# Speed.net
KiCad netlist of a schematic drawn in Altium Designer
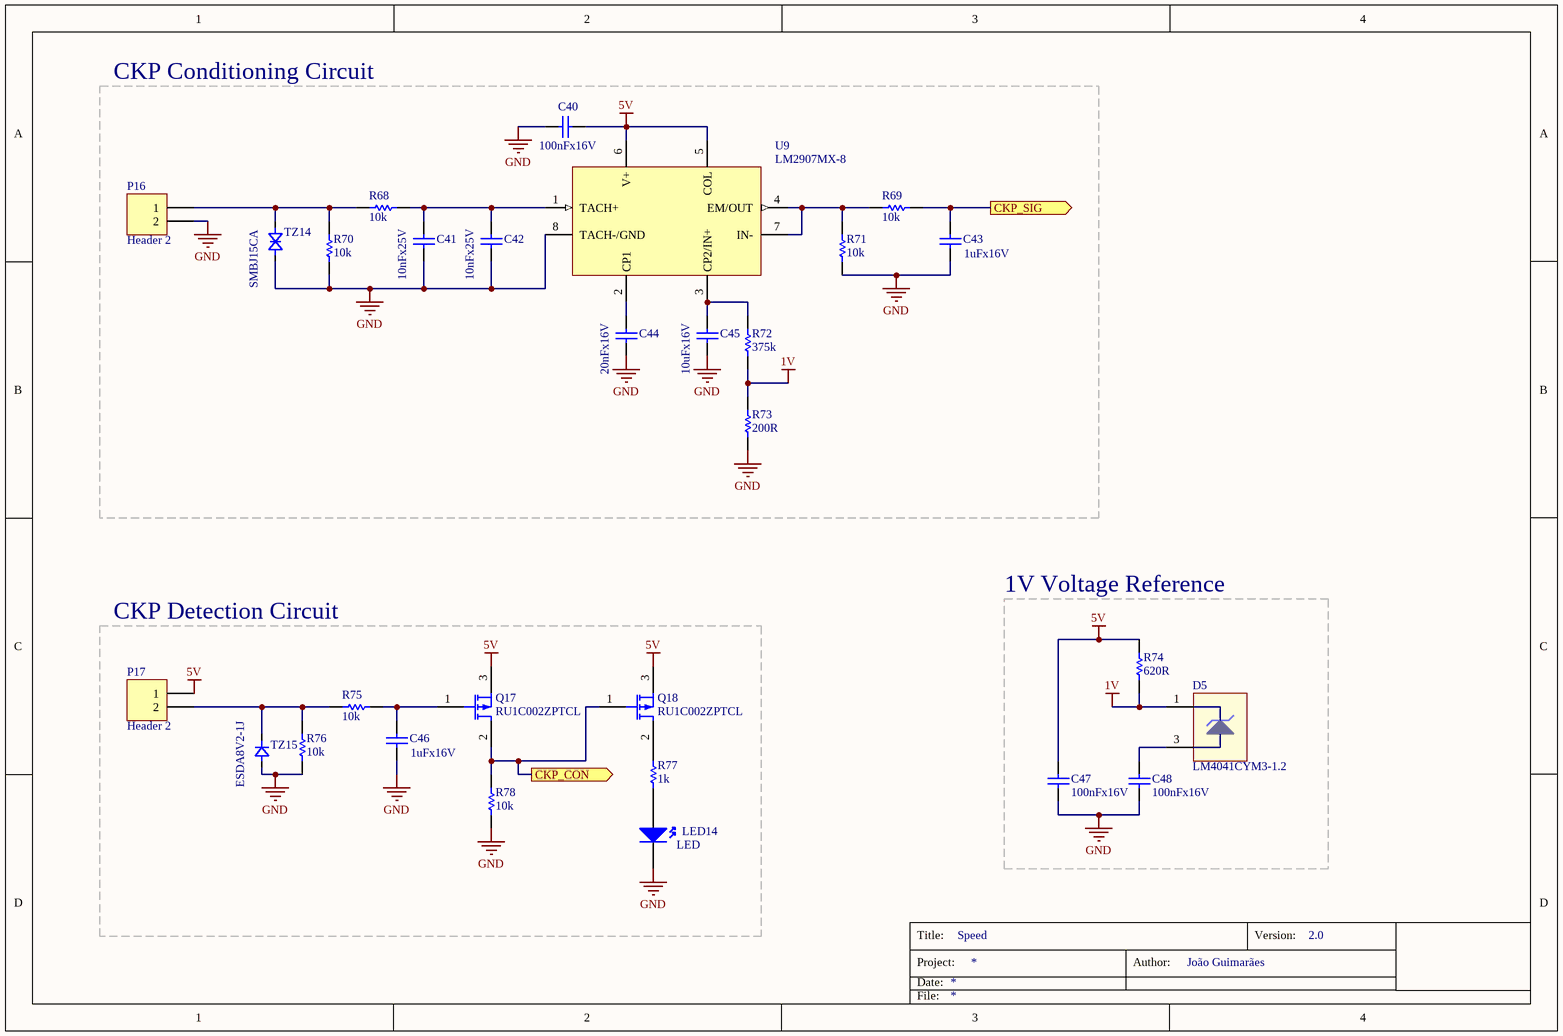
[diagram p0: Speed.SchDoc]

(export (version "E")
  (design (tool "Eeschema 10.0.6"))
  (components
    (comp (ref "C40")
      (value "100nFx16V")
      (footprint "DISC-0805")
      (description "Capacitor")
      (libsource (lib "IntLib") (part "Cap"))
    )
    (comp (ref "C41")
      (value "10nFx25V")
      (footprint "DISC-0805")
      (description "Capacitor")
      (libsource (lib "IntLib") (part "Cap"))
    )
    (comp (ref "C42")
      (value "10nFx25V")
      (footprint "DISC-0805")
      (description "Capacitor")
      (libsource (lib "IntLib") (part "Cap"))
    )
    (comp (ref "C43")
      (value "1uFx16V")
      (footprint "DISC-0805")
      (description "Capacitor")
      (libsource (lib "IntLib") (part "Cap"))
    )
    (comp (ref "C44")
      (value "20nFx16V")
      (footprint "DISC-0805")
      (description "Capacitor")
      (libsource (lib "IntLib") (part "Cap"))
    )
    (comp (ref "C45")
      (value "10uFx16V")
      (footprint "DISC-0805")
      (description "Capacitor")
      (libsource (lib "IntLib") (part "Cap"))
    )
    (comp (ref "C46")
      (value "1uFx16V")
      (footprint "DISC-0805")
      (description "Capacitor")
      (libsource (lib "IntLib") (part "Cap"))
    )
    (comp (ref "C47")
      (value "100nFx16V")
      (footprint "DISC-0805")
      (description "Capacitor")
      (libsource (lib "IntLib") (part "Cap"))
    )
    (comp (ref "C48")
      (value "100nFx16V")
      (footprint "DISC-0805")
      (description "Capacitor")
      (libsource (lib "IntLib") (part "Cap"))
    )
    (comp (ref "D5")
      (value "LM4041CYM3-1.2")
      (footprint "DISC-SOT-23")
      (description "Shunt Voltage References")
      (libsource (lib "IntLib") (part "LM4040"))
    )
    (comp (ref "LED14") (value "LED") (footprint "DISC-LED-0.1-PTH") (libsource (lib "IntLib") (part "LED")))
    (comp (ref "P16")
      (value "Header 2")
      (footprint "CON-FLEXWIRE-0.5MM2-1X2")
      (description "Header, 2-Pin")
      (fields (field (name "PUBLISHER") "Altium Limited"))
      (libsource (lib "IntLib") (part "Header 2"))
    )
    (comp (ref "P17")
      (value "Header 2")
      (footprint "CON-FLEXWIRE-0.5MM2-1X2")
      (description "Header, 2-Pin")
      (fields (field (name "PUBLISHER") "Altium Limited"))
      (libsource (lib "IntLib") (part "Header 2"))
    )
    (comp (ref "Q17")
      (value "RU1C002ZPTCL")
      (footprint "DISC-SOT-23")
      (description "P-Channel MOSFET")
      (libsource (lib "IntLib") (part "Transistor-PMOS"))
    )
    (comp (ref "Q18")
      (value "RU1C002ZPTCL")
      (footprint "DISC-SOT-23")
      (description "P-Channel MOSFET")
      (libsource (lib "IntLib") (part "Transistor-PMOS"))
    )
    (comp (ref "R68")
      (value "10k")
      (footprint "DISC-0805")
      (description "Resistor")
      (libsource (lib "IntLib") (part "Res"))
    )
    (comp (ref "R69")
      (value "10k")
      (footprint "DISC-0805")
      (description "Resistor")
      (libsource (lib "IntLib") (part "Res"))
    )
    (comp (ref "R70")
      (value "10k")
      (footprint "DISC-0805")
      (description "Resistor")
      (libsource (lib "IntLib") (part "Res"))
    )
    (comp (ref "R71")
      (value "10k")
      (footprint "DISC-0805")
      (description "Resistor")
      (libsource (lib "IntLib") (part "Res"))
    )
    (comp (ref "R72")
      (value "375k")
      (footprint "DISC-0805")
      (description "Resistor")
      (libsource (lib "IntLib") (part "Res"))
    )
    (comp (ref "R73")
      (value "200R")
      (footprint "DISC-0805")
      (description "Resistor")
      (libsource (lib "IntLib") (part "Res"))
    )
    (comp (ref "R74")
      (value "620R")
      (footprint "DISC-0805")
      (description "Resistor")
      (libsource (lib "IntLib") (part "Res"))
    )
    (comp (ref "R75")
      (value "10k")
      (footprint "DISC-0805")
      (description "Resistor")
      (libsource (lib "IntLib") (part "Res"))
    )
    (comp (ref "R76")
      (value "10k")
      (footprint "DISC-0805")
      (description "Resistor")
      (libsource (lib "IntLib") (part "Res"))
    )
    (comp (ref "R77")
      (value "1k")
      (footprint "DISC-0805")
      (description "Resistor")
      (libsource (lib "IntLib") (part "Res"))
    )
    (comp (ref "R78")
      (value "10k")
      (footprint "DISC-0805")
      (description "Resistor")
      (libsource (lib "IntLib") (part "Res"))
    )
    (comp (ref "TZ14")
      (value "SMBJ15CA")
      (footprint "DISC-DO214-AA")
      (description "TVZ-Bi-Directional")
      (libsource (lib "IntLib") (part "TVZ-Bi-Directional"))
    )
    (comp (ref "TZ15")
      (value "ESDA8V2-1J")
      (footprint "DISC-SOD-323")
      (description "TVZ-Unidirectional")
      (libsource (lib "IntLib") (part "TVZ-Unidirectional"))
    )
    (comp (ref "U9")
      (value "LM2907MX-8")
      (footprint "CI-SOIC-8")
      (description "Voltage to Frequency & Frequency to Voltage Frequency to Voltage Converter")
      (libsource (lib "IntLib") (part "LM2907MX-8"))
    )
  )
  (nets
    (net (code "1") (name "/CKP_CON") (class "Default")
      (node (ref "Q17") (pin "2") (pinfunction "D_2") (pintype "passive"))
      (node (ref "Q18") (pin "1") (pinfunction "G_1") (pintype "passive"))
      (node (ref "R78") (pin "2") (pinfunction "2_2") (pintype "passive"))
    )
    (net (code "2") (name "/CKP_SIG") (class "Default")
      (node (ref "C43") (pin "2") (pinfunction "2_2") (pintype "passive"))
      (node (ref "R69") (pin "2") (pinfunction "2_2") (pintype "passive"))
    )
    (net (code "3") (name "1V") (class "Default")
      (node (ref "D5") (pin "1") (pinfunction "A_1") (pintype "passive"))
      (node (ref "R72") (pin "2") (pinfunction "2_2") (pintype "passive"))
      (node (ref "R73") (pin "1") (pinfunction "1_1") (pintype "passive"))
      (node (ref "R74") (pin "2") (pinfunction "2_2") (pintype "passive"))
    )
    (net (code "4") (name "5V") (class "Default")
      (node (ref "C40") (pin "1") (pinfunction "1_1") (pintype "passive"))
      (node (ref "C47") (pin "1") (pinfunction "1_1") (pintype "passive"))
      (node (ref "P17") (pin "1") (pinfunction "1_1") (pintype "passive"))
      (node (ref "Q17") (pin "3") (pinfunction "S_3") (pintype "passive"))
      (node (ref "Q18") (pin "3") (pinfunction "S_3") (pintype "passive"))
      (node (ref "R74") (pin "1") (pinfunction "1_1") (pintype "passive"))
      (node (ref "U9") (pin "5") (pinfunction "COL_5") (pintype "passive"))
      (node (ref "U9") (pin "6") (pinfunction "V+_6") (pintype "power_in"))
    )
    (net (code "5") (name "GND") (class "Default")
      (node (ref "C40") (pin "2") (pinfunction "2_2") (pintype "passive"))
      (node (ref "C41") (pin "1") (pinfunction "1_1") (pintype "passive"))
      (node (ref "C42") (pin "1") (pinfunction "1_1") (pintype "passive"))
      (node (ref "C43") (pin "1") (pinfunction "1_1") (pintype "passive"))
      (node (ref "C44") (pin "1") (pinfunction "1_1") (pintype "passive"))
      (node (ref "C45") (pin "1") (pinfunction "1_1") (pintype "passive"))
      (node (ref "C46") (pin "1") (pinfunction "1_1") (pintype "passive"))
      (node (ref "C47") (pin "2") (pinfunction "2_2") (pintype "passive"))
      (node (ref "C48") (pin "2") (pinfunction "2_2") (pintype "passive"))
      (node (ref "LED14") (pin "2") (pinfunction "K_2") (pintype "passive"))
      (node (ref "P16") (pin "2") (pinfunction "2_2") (pintype "passive"))
      (node (ref "R70") (pin "2") (pinfunction "2_2") (pintype "passive"))
      (node (ref "R71") (pin "2") (pinfunction "2_2") (pintype "passive"))
      (node (ref "R73") (pin "2") (pinfunction "2_2") (pintype "passive"))
      (node (ref "R76") (pin "2") (pinfunction "2_2") (pintype "passive"))
      (node (ref "R78") (pin "1") (pinfunction "1_1") (pintype "passive"))
      (node (ref "TZ14") (pin "1") (pinfunction "A_1") (pintype "passive"))
      (node (ref "TZ15") (pin "1") (pinfunction "A_1") (pintype "passive"))
      (node (ref "U9") (pin "8") (pinfunction "TACH-/GND_8") (pintype "power_in"))
    )
    (net (code "6") (name "Net-(D5-K)") (class "Default")
      (node (ref "C48") (pin "1") (pinfunction "1_1") (pintype "passive"))
      (node (ref "D5") (pin "3") (pinfunction "K_3") (pintype "passive"))
    )
    (net (code "7") (name "Net-(LED14-A)") (class "Default")
      (node (ref "LED14") (pin "1") (pinfunction "A_1") (pintype "passive"))
      (node (ref "R77") (pin "1") (pinfunction "1_1") (pintype "passive"))
    )
    (net (code "8") (name "Net-(Q17-G)") (class "Default")
      (node (ref "C46") (pin "2") (pinfunction "2_2") (pintype "passive"))
      (node (ref "Q17") (pin "1") (pinfunction "G_1") (pintype "passive"))
      (node (ref "R75") (pin "2") (pinfunction "2_2") (pintype "passive"))
    )
    (net (code "9") (name "Net-(Q18-D)") (class "Default")
      (node (ref "Q18") (pin "2") (pinfunction "D_2") (pintype "passive"))
      (node (ref "R77") (pin "2") (pinfunction "2_2") (pintype "passive"))
    )
    (net (code "10") (name "Net-(TZ14-K)") (class "Default")
      (node (ref "P16") (pin "1") (pinfunction "1_1") (pintype "passive"))
      (node (ref "R68") (pin "2") (pinfunction "2_2") (pintype "passive"))
      (node (ref "R70") (pin "1") (pinfunction "1_1") (pintype "passive"))
      (node (ref "TZ14") (pin "2") (pinfunction "K_2") (pintype "passive"))
    )
    (net (code "11") (name "Net-(TZ15-C)") (class "Default")
      (node (ref "P17") (pin "2") (pinfunction "2_2") (pintype "passive"))
      (node (ref "R75") (pin "1") (pinfunction "1_1") (pintype "passive"))
      (node (ref "R76") (pin "1") (pinfunction "1_1") (pintype "passive"))
      (node (ref "TZ15") (pin "2") (pinfunction "C_2") (pintype "passive"))
    )
    (net (code "12") (name "Net-(U9-CP1)") (class "Default")
      (node (ref "C44") (pin "2") (pinfunction "2_2") (pintype "passive"))
      (node (ref "U9") (pin "2") (pinfunction "CP1_2") (pintype "passive"))
    )
    (net (code "13") (name "Net-(U9-CP2{slash}IN+)") (class "Default")
      (node (ref "C45") (pin "2") (pinfunction "2_2") (pintype "passive"))
      (node (ref "R72") (pin "1") (pinfunction "1_1") (pintype "passive"))
      (node (ref "U9") (pin "3") (pinfunction "CP2/IN+_3") (pintype "passive"))
    )
    (net (code "14") (name "Net-(U9-EM{slash}OUT)") (class "Default")
      (node (ref "R69") (pin "1") (pinfunction "1_1") (pintype "passive"))
      (node (ref "R71") (pin "1") (pinfunction "1_1") (pintype "passive"))
      (node (ref "U9") (pin "4") (pinfunction "EM/OUT_4") (pintype "output"))
      (node (ref "U9") (pin "7") (pinfunction "IN-_7") (pintype "passive"))
    )
    (net (code "15") (name "Net-(U9-TACH+)") (class "Default")
      (node (ref "C41") (pin "2") (pinfunction "2_2") (pintype "passive"))
      (node (ref "C42") (pin "2") (pinfunction "2_2") (pintype "passive"))
      (node (ref "R68") (pin "1") (pinfunction "1_1") (pintype "passive"))
      (node (ref "U9") (pin "1") (pinfunction "TACH+_1") (pintype "input"))
    )
    (net (code "16") (name "unconnected-(D5-Pad2)") (class "Default")
      (node (ref "D5") (pin "2") (pinfunction "2_2") (pintype "passive"))
    )
  )
)
